# pwr_sen_brd.net
KiCad netlist of a schematic drawn in Altium Designer
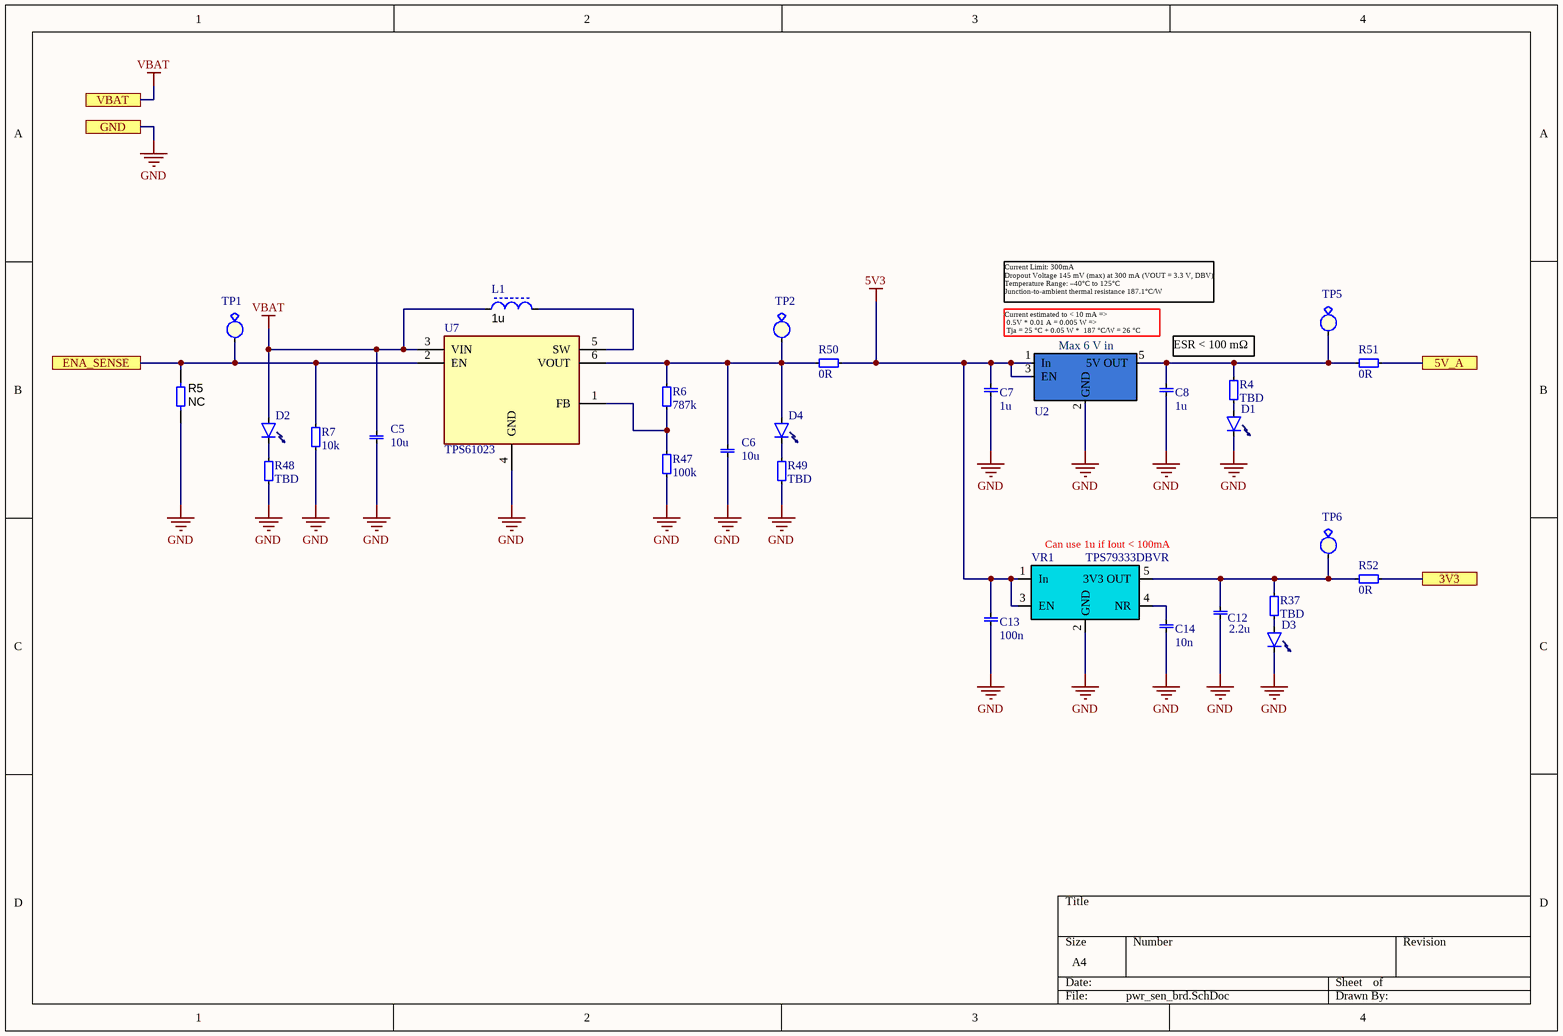
[diagram p0: pwr_sen_brd.SchDoc]

(export (version "E")
  (design (tool "Eeschema 10.0.6"))
  (components
    (comp (ref "C5")
      (value "10u")
      (footprint "1206, capasitor")
      (description "GRM155R61A106ME11D")
      (fields
        (field (name "MANUFACTURER PART NO") "CL31A106KAHNNNE")
        (field (name "Comment") "1206, capacitor")
      )
      (libsource (lib "jclib") (part "1206, capacitor"))
    )
    (comp (ref "C6")
      (value "10u")
      (footprint "1206, capasitor")
      (description "GRM155R61A106ME11D")
      (fields
        (field (name "MANUFACTURER PART NO") "CL31A106KAHNNNE")
        (field (name "Comment") "1206, capacitor")
      )
      (libsource (lib "jclib") (part "1206, capacitor"))
    )
    (comp (ref "C7")
      (value "1u")
      (footprint "0402 CAP")
      (fields
        (field (name "MANUFACTURER PART NO") "CL05A105KO5NNNC")
        (field (name "Comment") "0603, capacitor")
      )
      (libsource (lib "jclib") (part "0603, capacitor"))
    )
    (comp (ref "C8")
      (value "1u")
      (footprint "0402 CAP")
      (fields
        (field (name "MANUFACTURER PART NO") "CL05A105KO5NNNC")
        (field (name "Comment") "0603, capacitor")
      )
      (libsource (lib "jclib") (part "0603, capacitor"))
    )
    (comp (ref "C12")
      (value "2.2u")
      (footprint "0402 CAP")
      (fields
        (field (name "MANUFACTURER PART NO") "GRM155D71A225ME15D")
        (field (name "Comment") "0603, capacitor")
      )
      (libsource (lib "jclib") (part "0603, capacitor"))
    )
    (comp (ref "C13")
      (value "100n")
      (footprint "0402 CAP")
      (fields
        (field (name "MANUFACTURER PART NO") "GRM155R62A104KE14D")
        (field (name "Comment") "0603, capacitor")
      )
      (libsource (lib "jclib") (part "0603, capacitor"))
    )
    (comp (ref "C14")
      (value "10n")
      (footprint "0603 cap")
      (fields
        (field (name "MANUFACTURER PART NO") "CL10B103KB8NNNC")
        (field (name "Comment") "0603, capacitor")
      )
      (libsource (lib "sign_lib") (part "0603, capacitor"))
    )
    (comp (ref "D1")
      (value "0603, LED")
      (footprint "0603 LED")
      (fields (field (name "MANUFACTURER PART NO") "150060SS75003"))
      (libsource (lib "jclib") (part "0603, LED"))
    )
    (comp (ref "D2")
      (value "0603, LED")
      (footprint "0603 LED")
      (fields (field (name "MANUFACTURER PART NO") "5988081107F"))
      (libsource (lib "jclib") (part "0603, LED"))
    )
    (comp (ref "D3")
      (value "0603, LED")
      (footprint "0603 LED")
      (fields (field (name "MANUFACTURER PART NO") "150060SS75003"))
      (libsource (lib "jclib") (part "0603, LED"))
    )
    (comp (ref "D4")
      (value "0603, LED")
      (footprint "0603 LED")
      (fields (field (name "MANUFACTURER PART NO") "5988081107F"))
      (libsource (lib "jclib") (part "0603, LED"))
    )
    (comp (ref "L1")
      (value "1u")
      (footprint "74404043010A")
      (description "Shielded Power Inductor with Ferrite Core")
      (fields (field (name "PARTNUMBER") "74404043010A") (field (name "Comment") "Inductor, 74404043010A"))
      (libsource (lib "urad") (part "Inductor, 74404043010A"))
    )
    (comp (ref "R4")
      (value "TBD")
      (footprint "0402 res")
      (fields (field (name "Comment") "0603, resistor"))
      (libsource (lib "jclib") (part "0603, resistor"))
    )
    (comp (ref "R5")
      (value "NC")
      (footprint "0603")
      (fields (field (name "Comment") "RES, 0603"))
      (libsource (lib "urad") (part "RES, 0603"))
    )
    (comp (ref "R6")
      (value "787k")
      (footprint "0402 res")
      (description "RES 787K OHM 1% 1/16W 0402")
      (fields
        (field (name "MANUFACTURER PART NO") "RC0402FR-07787KL")
        (field (name "Comment") "0603, resistor")
      )
      (libsource (lib "jclib") (part "0603, resistor"))
    )
    (comp (ref "R7")
      (value "10k")
      (footprint "0402 res")
      (fields
        (field (name "MANUFACTURER PART NO") "311-10.0KLRCT-ND")
        (field (name "Comment") "0603, resistor")
      )
      (libsource (lib "jclib") (part "0603, resistor"))
    )
    (comp (ref "R37")
      (value "TBD")
      (footprint "0402 res")
      (fields (field (name "Comment") "0603, resistor"))
      (libsource (lib "jclib") (part "0603, resistor"))
    )
    (comp (ref "R47")
      (value "100k")
      (footprint "0402 res")
      (fields
        (field (name "MANUFACTURER PART NO") "RC0402FR-07100KL")
        (field (name "Comment") "0603, resistor")
      )
      (libsource (lib "jclib") (part "0603, resistor"))
    )
    (comp (ref "R48")
      (value "TBD")
      (footprint "0402 res")
      (fields (field (name "Comment") "0603, resistor"))
      (libsource (lib "jclib") (part "0603, resistor"))
    )
    (comp (ref "R49")
      (value "TBD")
      (footprint "0402 res")
      (fields (field (name "Comment") "0603, resistor"))
      (libsource (lib "jclib") (part "0603, resistor"))
    )
    (comp (ref "R50")
      (value "0R")
      (footprint "0603")
      (fields
        (field (name "MANUFACTURER PART NO") "CRCW06030000Z0EA")
        (field (name "Comment") "0603, resistor")
      )
      (libsource (lib "jclib") (part "0603, resistor"))
    )
    (comp (ref "R51")
      (value "0R")
      (footprint "0603")
      (fields
        (field (name "MANUFACTURER PART NO") "CRCW06030000Z0EA")
        (field (name "Comment") "0603, resistor")
      )
      (libsource (lib "jclib") (part "0603, resistor"))
    )
    (comp (ref "R52")
      (value "0R")
      (footprint "0603")
      (fields
        (field (name "MANUFACTURER PART NO") "CRCW06030000Z0EA")
        (field (name "Comment") "0603, resistor")
      )
      (libsource (lib "jclib") (part "0603, resistor"))
    )
    (comp (ref "TP1")
      (value "Test Point")
      (footprint "TESTPOINT_SMD")
      (libsource (lib "jclib") (part "Test Point"))
    )
    (comp (ref "TP2")
      (value "Test Point")
      (footprint "TESTPOINT_SMD")
      (libsource (lib "jclib") (part "Test Point"))
    )
    (comp (ref "TP5")
      (value "Test Point")
      (footprint "TESTPOINT_SMD")
      (libsource (lib "jclib") (part "Test Point"))
    )
    (comp (ref "TP6")
      (value "Test Point")
      (footprint "TESTPOINT_SMD")
      (libsource (lib "jclib") (part "Test Point"))
    )
    (comp (ref "U2")
      (value "TPS7A20")
      (footprint "SOT23-5")
      (description "5V and 300-mA, Ultra-Low-Noise, Low-IQ, High PSRR LDO")
      (fields (field (name "MANUFACTURER PART NO") "TPS7A2050PDBVR"))
      (libsource (lib "jclib") (part "TPS7A20"))
    )
    (comp (ref "U7")
      (value "TPS61023")
      (footprint "SOT50P160X60-6N")
      (description "TPS61023 3.7-A Boost Converter with 0.5-V Ultra-low Input Voltage")
      (fields (field (name "MANUFACTURER PART NO") "TPS61023DRLT"))
      (libsource (lib "urad") (part "TPS61023"))
    )
    (comp (ref "VR1")
      (value "TPS79333DBVR")
      (footprint "SOT23-5")
      (description "Low Dropout Regulators(LDO) Positive Fixed 180mV @ 200mA 5.5V 3.3V 200mA SOT-23-5 RoHS")
      (libsource (lib "sign_lib") (part "TPS79333DBVR"))
    )
  )
  (nets
    (net (code "1") (name "/3V3") (class "Default")
      (node (ref "R52") (pin "0") (pinfunction "0_0") (pintype "passive"))
    )
    (net (code "2") (name "/5V_A") (class "Default")
      (node (ref "R51") (pin "0") (pinfunction "0_0") (pintype "passive"))
    )
    (net (code "3") (name "/ENA_SENSE") (class "Default")
      (node (ref "R5") (pin "2") (pinfunction "2_2") (pintype "passive"))
      (node (ref "R7") (pin "0") (pinfunction "0_0") (pintype "passive"))
      (node (ref "TP1") (pin "0") (pinfunction "0_0") (pintype "passive"))
      (node (ref "U7") (pin "2") (pinfunction "EN_2") (pintype "passive"))
    )
    (net (code "4") (name "5V3") (class "Default")
      (node (ref "C13") (pin "1") (pinfunction "1_1") (pintype "passive"))
      (node (ref "C7") (pin "1") (pinfunction "1_1") (pintype "passive"))
      (node (ref "R50") (pin "0") (pinfunction "0_0") (pintype "passive"))
      (node (ref "U2") (pin "1") (pinfunction "In_1") (pintype "passive"))
      (node (ref "U2") (pin "3") (pinfunction "EN_3") (pintype "passive"))
      (node (ref "VR1") (pin "1") (pinfunction "In_1") (pintype "passive"))
      (node (ref "VR1") (pin "3") (pinfunction "EN_3") (pintype "passive"))
    )
    (net (code "5") (name "GND") (class "Default")
      (node (ref "C12") (pin "0") (pinfunction "0_0") (pintype "passive"))
      (node (ref "C13") (pin "0") (pinfunction "0_0") (pintype "passive"))
      (node (ref "C14") (pin "0") (pinfunction "0_0") (pintype "passive"))
      (node (ref "C5") (pin "0") (pinfunction "0_0") (pintype "passive"))
      (node (ref "C6") (pin "0") (pinfunction "0_0") (pintype "passive"))
      (node (ref "C7") (pin "0") (pinfunction "0_0") (pintype "passive"))
      (node (ref "C8") (pin "0") (pinfunction "0_0") (pintype "passive"))
      (node (ref "D1") (pin "0") (pinfunction "Cathode_0") (pintype "passive"))
      (node (ref "D3") (pin "0") (pinfunction "Cathode_0") (pintype "passive"))
      (node (ref "R47") (pin "1") (pinfunction "1_1") (pintype "passive"))
      (node (ref "R48") (pin "1") (pinfunction "1_1") (pintype "passive"))
      (node (ref "R49") (pin "1") (pinfunction "1_1") (pintype "passive"))
      (node (ref "R5") (pin "1") (pinfunction "1_1") (pintype "passive"))
      (node (ref "R7") (pin "1") (pinfunction "1_1") (pintype "passive"))
      (node (ref "U2") (pin "2") (pinfunction "GND_2") (pintype "passive"))
      (node (ref "U7") (pin "4") (pinfunction "GND_4") (pintype "power_in"))
      (node (ref "VR1") (pin "2") (pinfunction "GND_2") (pintype "passive"))
    )
    (net (code "6") (name "Net-(D1-Pad1)") (class "Default")
      (node (ref "D1") (pin "1") (pinfunction "1_1") (pintype "passive"))
      (node (ref "R4") (pin "0") (pinfunction "0_0") (pintype "passive"))
    )
    (net (code "7") (name "Net-(D2-Cathode)") (class "Default")
      (node (ref "D2") (pin "0") (pinfunction "Cathode_0") (pintype "passive"))
      (node (ref "R48") (pin "0") (pinfunction "0_0") (pintype "passive"))
    )
    (net (code "8") (name "Net-(D3-Pad1)") (class "Default")
      (node (ref "D3") (pin "1") (pinfunction "1_1") (pintype "passive"))
      (node (ref "R37") (pin "0") (pinfunction "0_0") (pintype "passive"))
    )
    (net (code "9") (name "Net-(D4-Cathode)") (class "Default")
      (node (ref "D4") (pin "0") (pinfunction "Cathode_0") (pintype "passive"))
      (node (ref "R49") (pin "0") (pinfunction "0_0") (pintype "passive"))
    )
    (net (code "10") (name "Net-(U2-5V_OUT)") (class "Default")
      (node (ref "C8") (pin "1") (pinfunction "1_1") (pintype "passive"))
      (node (ref "R4") (pin "1") (pinfunction "1_1") (pintype "passive"))
      (node (ref "R51") (pin "1") (pinfunction "1_1") (pintype "passive"))
      (node (ref "TP5") (pin "0") (pinfunction "0_0") (pintype "passive"))
      (node (ref "U2") (pin "5") (pinfunction "5V_OUT_5") (pintype "passive"))
    )
    (net (code "11") (name "Net-(U7-FB)") (class "Default")
      (node (ref "R47") (pin "0") (pinfunction "0_0") (pintype "passive"))
      (node (ref "R6") (pin "1") (pinfunction "1_1") (pintype "passive"))
      (node (ref "U7") (pin "1") (pinfunction "FB_1") (pintype "passive"))
    )
    (net (code "12") (name "Net-(U7-SW)") (class "Default")
      (node (ref "L1") (pin "1") (pinfunction "1_1") (pintype "passive"))
      (node (ref "U7") (pin "5") (pinfunction "SW_5") (pintype "passive"))
    )
    (net (code "13") (name "Net-(U7-VOUT)") (class "Default")
      (node (ref "C6") (pin "1") (pinfunction "1_1") (pintype "passive"))
      (node (ref "D4") (pin "1") (pinfunction "1_1") (pintype "passive"))
      (node (ref "R50") (pin "1") (pinfunction "1_1") (pintype "passive"))
      (node (ref "R6") (pin "0") (pinfunction "0_0") (pintype "passive"))
      (node (ref "TP2") (pin "0") (pinfunction "0_0") (pintype "passive"))
      (node (ref "U7") (pin "6") (pinfunction "VOUT_6") (pintype "passive"))
    )
    (net (code "14") (name "Net-(VR1-3V3_OUT)") (class "Default")
      (node (ref "C12") (pin "1") (pinfunction "1_1") (pintype "passive"))
      (node (ref "R37") (pin "1") (pinfunction "1_1") (pintype "passive"))
      (node (ref "R52") (pin "1") (pinfunction "1_1") (pintype "passive"))
      (node (ref "TP6") (pin "0") (pinfunction "0_0") (pintype "passive"))
      (node (ref "VR1") (pin "5") (pinfunction "3V3_OUT_5") (pintype "passive"))
    )
    (net (code "15") (name "Net-(VR1-NR)") (class "Default")
      (node (ref "C14") (pin "1") (pinfunction "1_1") (pintype "passive"))
      (node (ref "VR1") (pin "4") (pinfunction "NR_4") (pintype "passive"))
    )
    (net (code "16") (name "VBAT") (class "Default")
      (node (ref "C5") (pin "1") (pinfunction "1_1") (pintype "passive"))
      (node (ref "D2") (pin "1") (pinfunction "1_1") (pintype "passive"))
      (node (ref "L1") (pin "2") (pinfunction "2_2") (pintype "passive"))
      (node (ref "U7") (pin "3") (pinfunction "VIN_3") (pintype "passive"))
    )
  )
)
